# PROC054D_SMA_SMP_Connectors.net
KiCad netlist of a schematic drawn in Altium Designer
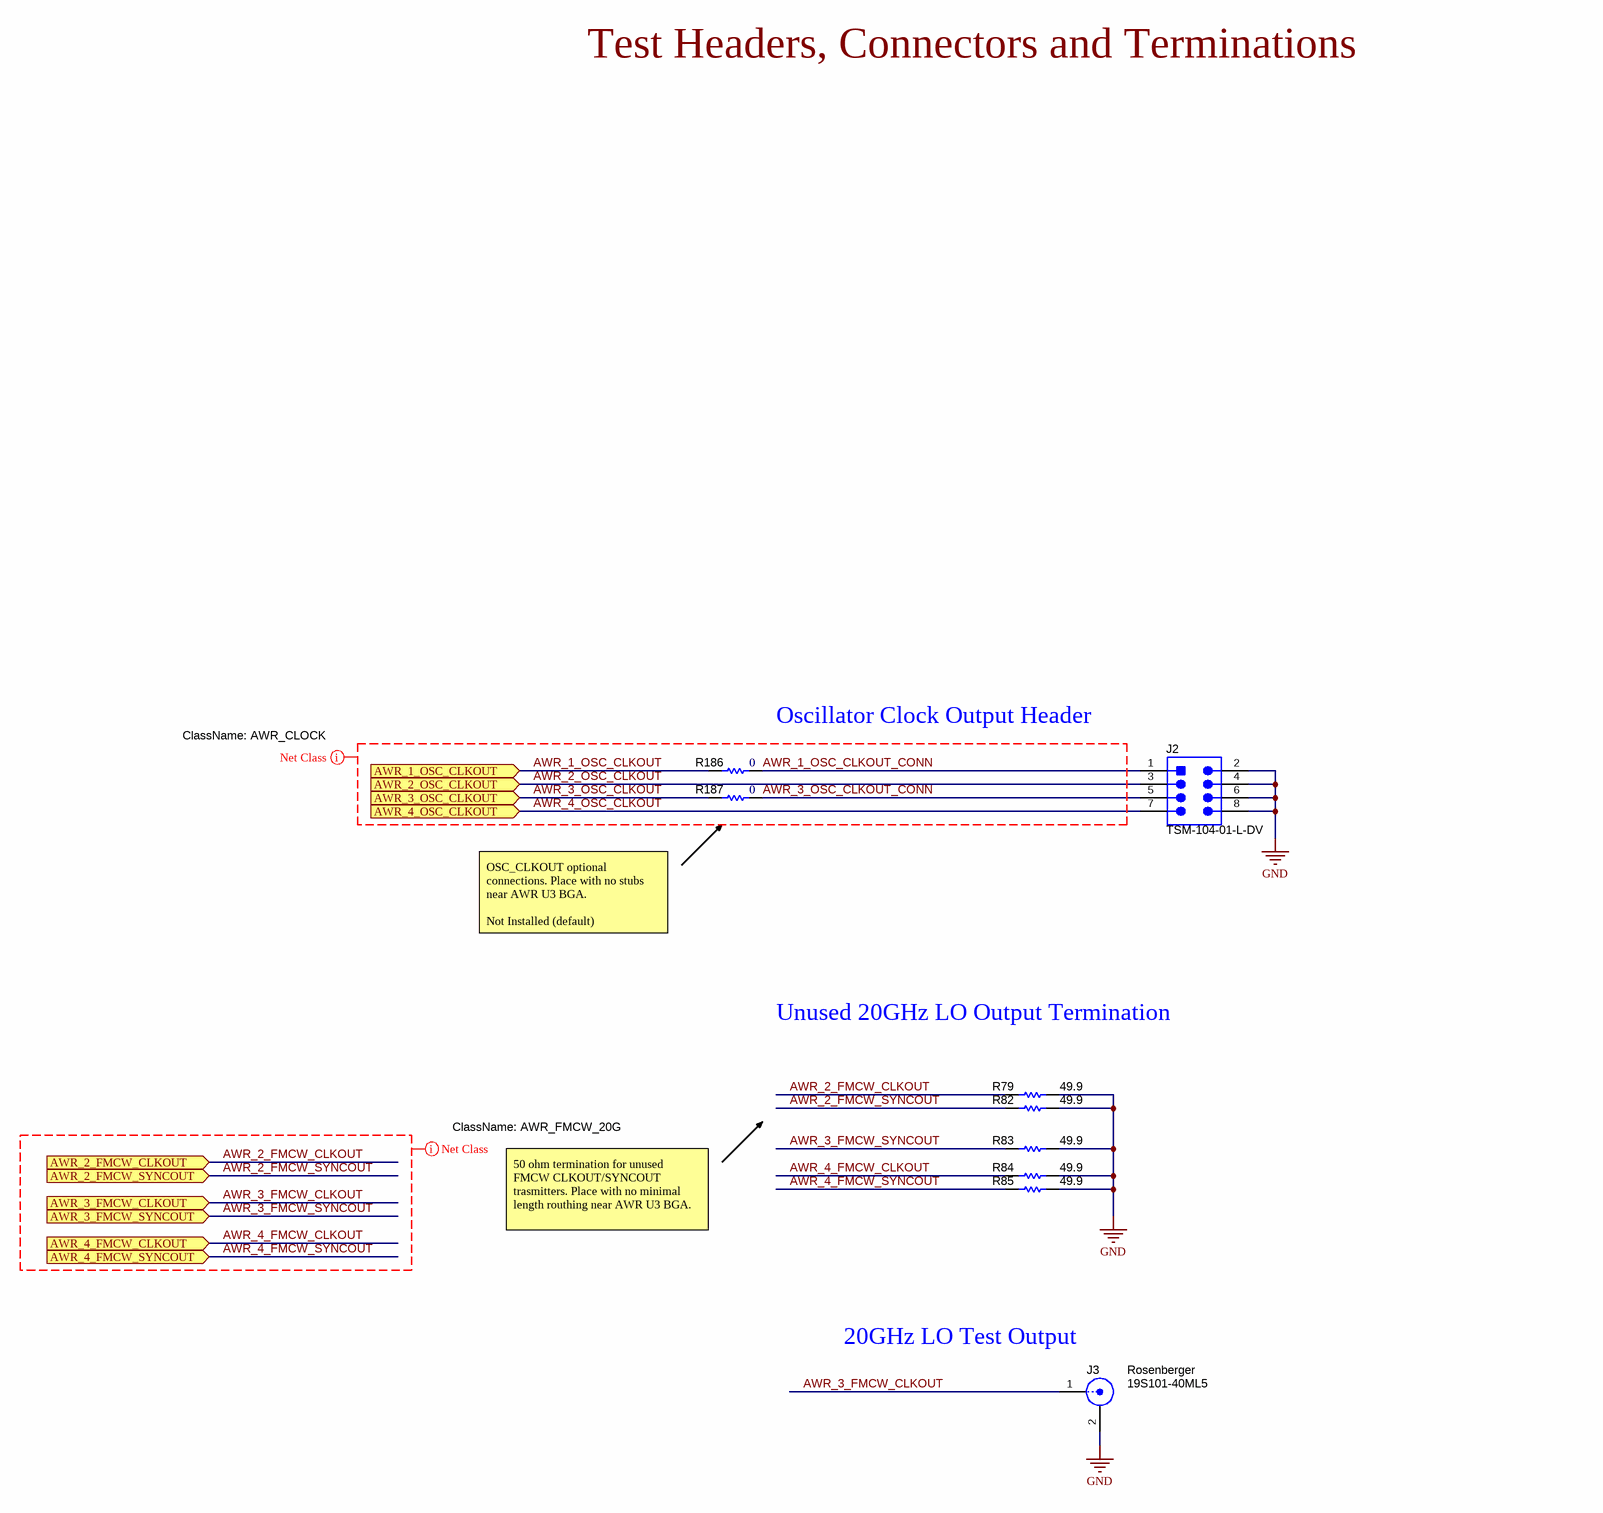
[diagram p0: PROC054D_SMA_SMP_Connectors.SchDoc]

(export (version "E")
  (design (tool "Eeschema 10.0.6"))
  (components
    (comp (ref "J2")
      (value "TSM-104-01-L-DV")
      (footprint "Samtec_TSM-104-01-x-DV")
      (description "Header, 2.54mm, 4x2, Gold, SMT")
      (fields (field (name "MANUFACTURER") "Samtec"))
      (libsource (lib "Altium Vault - TI") (part "Header_4x2"))
    )
    (comp (ref "J3")
      (value "19S101-40ML5")
      (footprint "19S101_40ML5")
      (description "Connector, RF 50 Ohms, SMT")
      (fields (field (name "MANUFACTURER") "Rosenberger") (field (name "PUBLISHER") "Texas Instruments"))
      (libsource (lib "Altium Vault - TI") (part "CMP-0055458-1"))
    )
    (comp (ref "R79")
      (value "CRCW040249R9FKED")
      (footprint "0402")
      (description "RES, 49.9, 1%, 0.063 W, AEC-Q200 Grade 0, 0402")
      (fields (field (name "MANUFACTURER") "Vishay-Dale") (field (name "VALUEDISPLAYED") "49.9"))
      (libsource (lib "Altium Vault - TI") (part "Resistor"))
    )
    (comp (ref "R82")
      (value "CRCW040249R9FKED")
      (footprint "0402")
      (description "RES, 49.9, 1%, 0.063 W, AEC-Q200 Grade 0, 0402")
      (fields (field (name "MANUFACTURER") "Vishay-Dale") (field (name "VALUEDISPLAYED") "49.9"))
      (libsource (lib "Altium Vault - TI") (part "Resistor"))
    )
    (comp (ref "R83")
      (value "CRCW040249R9FKED")
      (footprint "0402")
      (description "RES, 49.9, 1%, 0.063 W, AEC-Q200 Grade 0, 0402")
      (fields (field (name "MANUFACTURER") "Vishay-Dale") (field (name "VALUEDISPLAYED") "49.9"))
      (libsource (lib "Altium Vault - TI") (part "Resistor"))
    )
    (comp (ref "R84")
      (value "CRCW040249R9FKED")
      (footprint "0402")
      (description "RES, 49.9, 1%, 0.063 W, AEC-Q200 Grade 0, 0402")
      (fields (field (name "MANUFACTURER") "Vishay-Dale") (field (name "VALUEDISPLAYED") "49.9"))
      (libsource (lib "Altium Vault - TI") (part "Resistor"))
    )
    (comp (ref "R85")
      (value "CRCW040249R9FKED")
      (footprint "0402")
      (description "RES, 49.9, 1%, 0.063 W, AEC-Q200 Grade 0, 0402")
      (fields (field (name "MANUFACTURER") "Vishay-Dale") (field (name "VALUEDISPLAYED") "49.9"))
      (libsource (lib "Altium Vault - TI") (part "Resistor"))
    )
    (comp (ref "R186")
      (value "ERJ-2GE0R00X")
      (footprint "0402S")
      (description "RES, 0, 5%, 0.1 W, AEC-Q200 Grade 0, 0402")
      (fields (field (name "MANUFACTURER") "Panasonic") (field (name "VALUEDISPLAYED") "0"))
      (libsource (lib "Altium Vault - TI") (part "Resistor"))
    )
    (comp (ref "R187")
      (value "ERJ-2GE0R00X")
      (footprint "0402S")
      (description "RES, 0, 5%, 0.1 W, AEC-Q200 Grade 0, 0402")
      (fields (field (name "MANUFACTURER") "Panasonic") (field (name "VALUEDISPLAYED") "0"))
      (libsource (lib "Altium Vault - TI") (part "Resistor"))
    )
  )
  (nets
    (net (code "1") (name "/AWR_1_OSC_CLKOUT") (class "Default")
      (node (ref "R186") (pin "1") (pinfunction "1_1") (pintype "passive"))
    )
    (net (code "2") (name "/AWR_1_OSC_CLKOUT_CONN") (class "Default")
      (node (ref "J2") (pin "1") (pinfunction "1_1") (pintype "passive"))
      (node (ref "R186") (pin "2") (pinfunction "2_2") (pintype "passive"))
    )
    (net (code "3") (name "/AWR_2_FMCW_CLKOUT") (class "Default")
      (node (ref "R79") (pin "1") (pinfunction "1_1") (pintype "passive"))
    )
    (net (code "4") (name "/AWR_2_FMCW_SYNCOUT") (class "Default")
      (node (ref "R82") (pin "1") (pinfunction "1_1") (pintype "passive"))
    )
    (net (code "5") (name "/AWR_2_OSC_CLKOUT") (class "Default")
      (node (ref "J2") (pin "3") (pinfunction "3_3") (pintype "passive"))
    )
    (net (code "6") (name "/AWR_3_FMCW_CLKOUT") (class "Default")
      (node (ref "J3") (pin "1") (pinfunction "1_1") (pintype "passive"))
    )
    (net (code "7") (name "/AWR_3_FMCW_SYNCOUT") (class "Default")
      (node (ref "R83") (pin "1") (pinfunction "1_1") (pintype "passive"))
    )
    (net (code "8") (name "/AWR_3_OSC_CLKOUT") (class "Default")
      (node (ref "R187") (pin "1") (pinfunction "1_1") (pintype "passive"))
    )
    (net (code "9") (name "/AWR_3_OSC_CLKOUT_CONN") (class "Default")
      (node (ref "J2") (pin "5") (pinfunction "5_5") (pintype "passive"))
      (node (ref "R187") (pin "2") (pinfunction "2_2") (pintype "passive"))
    )
    (net (code "10") (name "/AWR_4_FMCW_CLKOUT") (class "Default")
      (node (ref "R84") (pin "1") (pinfunction "1_1") (pintype "passive"))
    )
    (net (code "11") (name "/AWR_4_FMCW_SYNCOUT") (class "Default")
      (node (ref "R85") (pin "1") (pinfunction "1_1") (pintype "passive"))
    )
    (net (code "12") (name "/AWR_4_OSC_CLKOUT") (class "Default")
      (node (ref "J2") (pin "7") (pinfunction "7_7") (pintype "passive"))
    )
    (net (code "13") (name "GND") (class "Default")
      (node (ref "J2") (pin "2") (pinfunction "2_2") (pintype "passive"))
      (node (ref "J2") (pin "4") (pinfunction "4_4") (pintype "passive"))
      (node (ref "J2") (pin "6") (pinfunction "6_6") (pintype "passive"))
      (node (ref "J2") (pin "8") (pinfunction "8_8") (pintype "passive"))
      (node (ref "J3") (pin "2") (pinfunction "2_2") (pintype "passive"))
      (node (ref "R79") (pin "2") (pinfunction "2_2") (pintype "passive"))
      (node (ref "R82") (pin "2") (pinfunction "2_2") (pintype "passive"))
      (node (ref "R83") (pin "2") (pinfunction "2_2") (pintype "passive"))
      (node (ref "R84") (pin "2") (pinfunction "2_2") (pintype "passive"))
      (node (ref "R85") (pin "2") (pinfunction "2_2") (pintype "passive"))
    )
  )
)
